# QFN-20_0_5mm.net
KiCad netlist of a schematic drawn in EAGLE
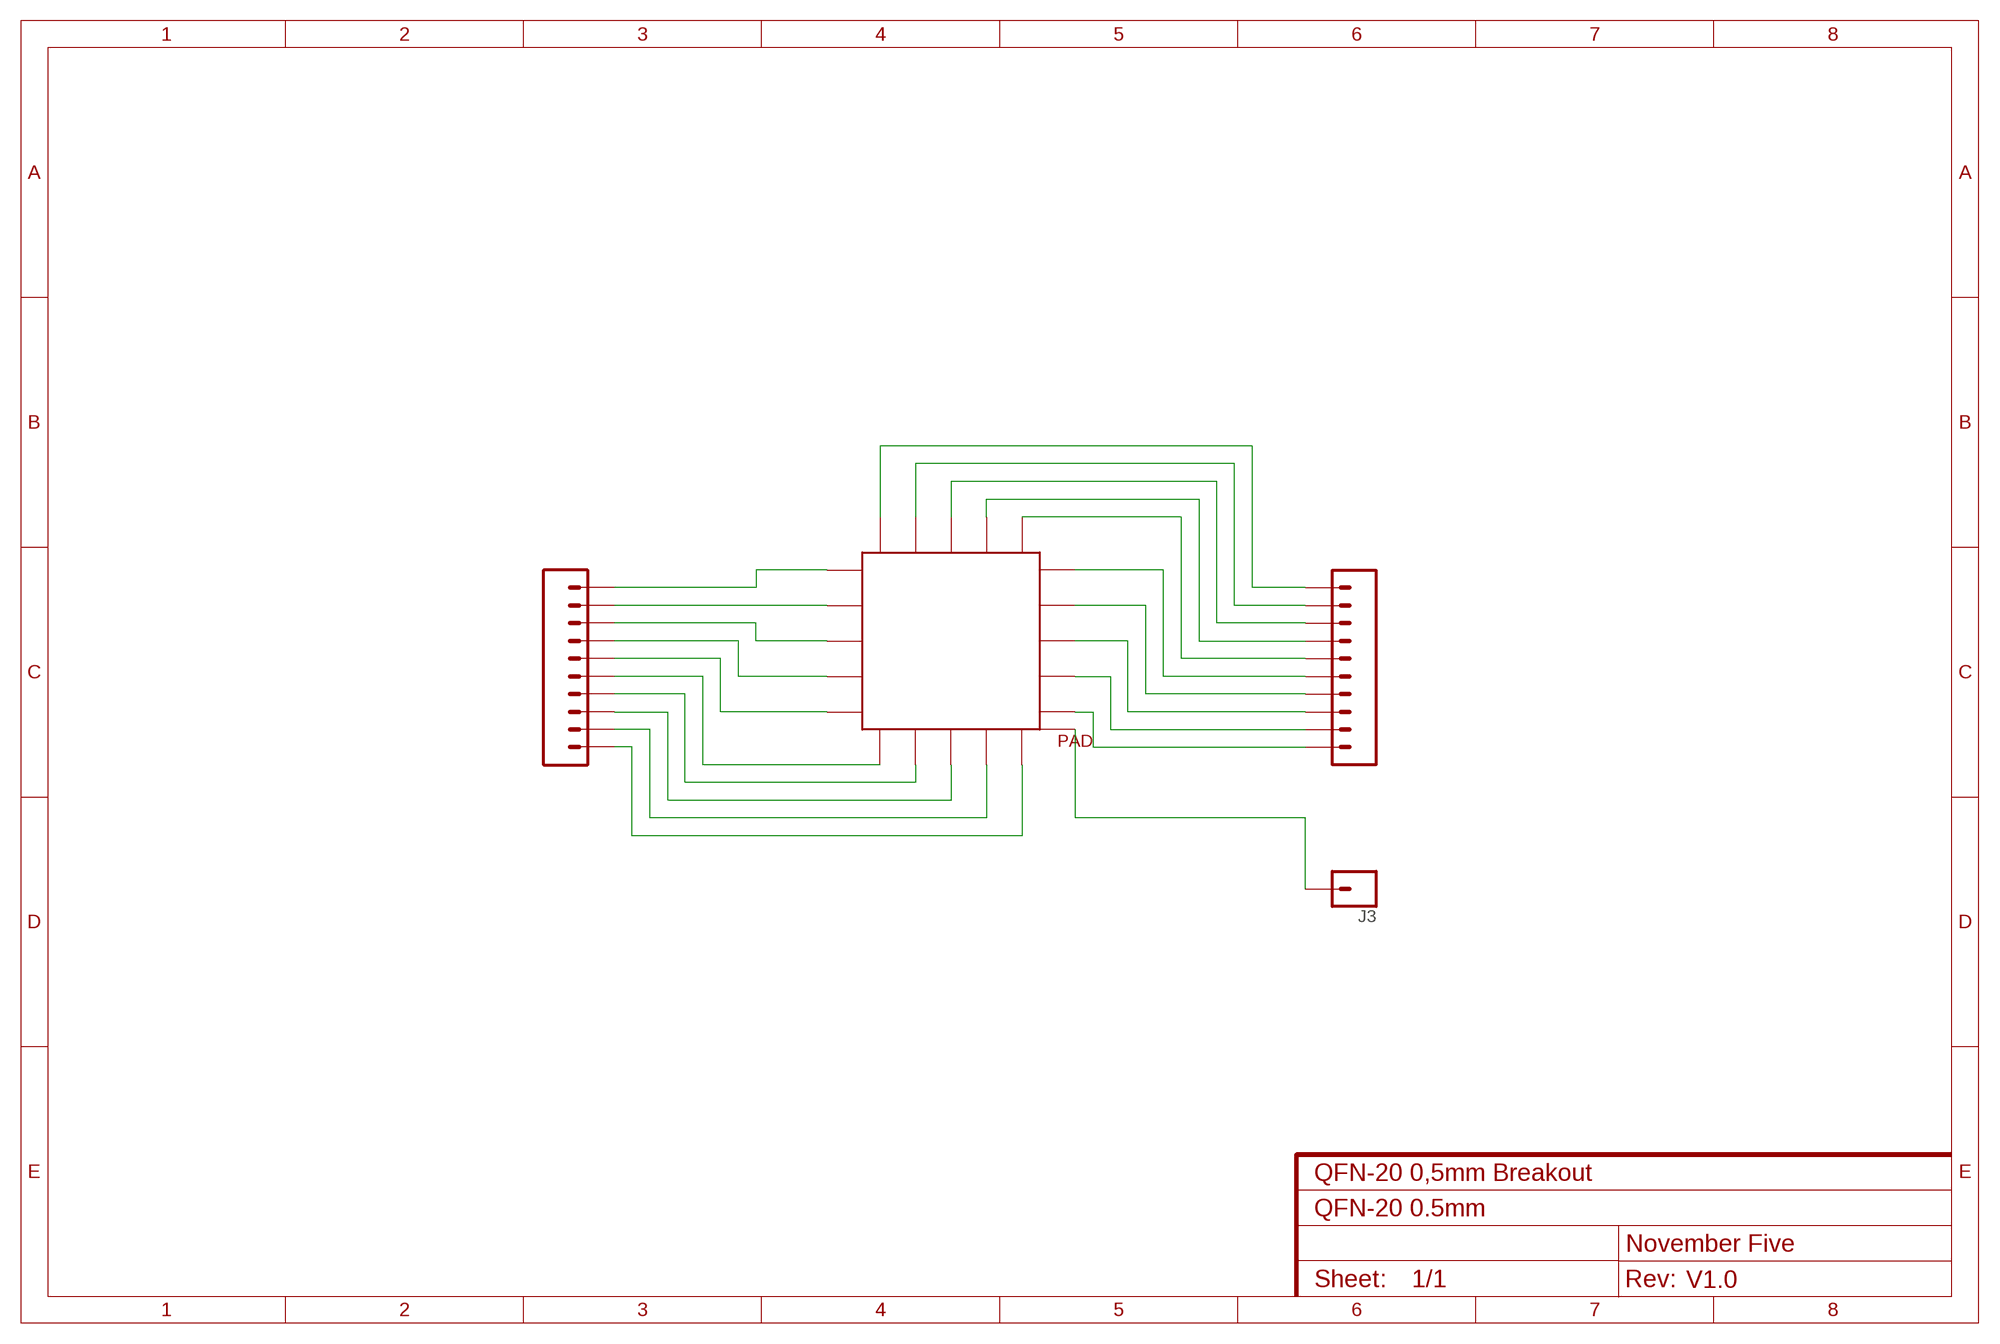
[diagram p0: schematic, sheet 1]

(export (version "E")
  (design (tool "Eeschema 10.0.6"))
  (components
    (comp (ref "J1")
      (value "CONN_10\"")
      (footprint "eagle-import:1X10")
      (libsource (lib "eagle-import") (part "CONN_10{dblquote}"))
    )
    (comp (ref "J2")
      (value "CONN_10\"")
      (footprint "eagle-import:1X10")
      (libsource (lib "eagle-import") (part "CONN_10{dblquote}"))
    )
    (comp (ref "J3")
      (value "CONN_01")
      (footprint "eagle-import:1X01")
      (libsource (lib "eagle-import") (part "CONN_01"))
    )
    (comp (ref "U$1")
      (value "QFN-20_0,5MM")
      (footprint "eagle-import:QFN20_0,5MM")
      (libsource (lib "eagle-import") (part "QFN-20_0,5MM"))
    )
  )
  (nets
    (net (code "1") (name "Net-(U$1-PAD)") (class "Default")
      (node (ref "J3") (pin "1") (pinfunction "1_1") (pintype "passive"))
      (node (ref "U$1") (pin "0") (pinfunction "PAD_0") (pintype "power_in"))
    )
    (net (code "2") (name "Net-(U$1-PIN1)") (class "Default")
      (node (ref "J1") (pin "1") (pinfunction "1_1") (pintype "passive"))
      (node (ref "U$1") (pin "1") (pinfunction "PIN1_1") (pintype "bidirectional"))
    )
    (net (code "3") (name "Net-(U$1-PIN2)") (class "Default")
      (node (ref "J1") (pin "2") (pinfunction "2_2") (pintype "passive"))
      (node (ref "U$1") (pin "2") (pinfunction "PIN2_2") (pintype "bidirectional"))
    )
    (net (code "4") (name "Net-(U$1-PIN3)") (class "Default")
      (node (ref "J1") (pin "3") (pinfunction "3_3") (pintype "passive"))
      (node (ref "U$1") (pin "3") (pinfunction "PIN3_3") (pintype "bidirectional"))
    )
    (net (code "5") (name "Net-(U$1-PIN4)") (class "Default")
      (node (ref "J1") (pin "4") (pinfunction "4_4") (pintype "passive"))
      (node (ref "U$1") (pin "4") (pinfunction "PIN4_4") (pintype "bidirectional"))
    )
    (net (code "6") (name "Net-(U$1-PIN5)") (class "Default")
      (node (ref "J1") (pin "5") (pinfunction "5_5") (pintype "passive"))
      (node (ref "U$1") (pin "5") (pinfunction "PIN5_5") (pintype "bidirectional"))
    )
    (net (code "7") (name "Net-(U$1-PIN6)") (class "Default")
      (node (ref "J1") (pin "6") (pinfunction "6_6") (pintype "passive"))
      (node (ref "U$1") (pin "6") (pinfunction "PIN6_6") (pintype "bidirectional"))
    )
    (net (code "8") (name "Net-(U$1-PIN7)") (class "Default")
      (node (ref "J1") (pin "7") (pinfunction "7_7") (pintype "passive"))
      (node (ref "U$1") (pin "7") (pinfunction "PIN7_7") (pintype "bidirectional"))
    )
    (net (code "9") (name "Net-(U$1-PIN8)") (class "Default")
      (node (ref "J1") (pin "8") (pinfunction "8_8") (pintype "passive"))
      (node (ref "U$1") (pin "8") (pinfunction "PIN8_8") (pintype "bidirectional"))
    )
    (net (code "10") (name "Net-(U$1-PIN9)") (class "Default")
      (node (ref "J1") (pin "9") (pinfunction "9_9") (pintype "passive"))
      (node (ref "U$1") (pin "9") (pinfunction "PIN9_9") (pintype "bidirectional"))
    )
    (net (code "11") (name "Net-(U$1-PIN10)") (class "Default")
      (node (ref "J1") (pin "10") (pinfunction "10_10") (pintype "passive"))
      (node (ref "U$1") (pin "10") (pinfunction "PIN10_10") (pintype "bidirectional"))
    )
    (net (code "12") (name "Net-(U$1-PIN11)") (class "Default")
      (node (ref "J2") (pin "10") (pinfunction "10_10") (pintype "passive"))
      (node (ref "U$1") (pin "11") (pinfunction "PIN11_11") (pintype "bidirectional"))
    )
    (net (code "13") (name "Net-(U$1-PIN12)") (class "Default")
      (node (ref "J2") (pin "9") (pinfunction "9_9") (pintype "passive"))
      (node (ref "U$1") (pin "12") (pinfunction "PIN12_12") (pintype "bidirectional"))
    )
    (net (code "14") (name "Net-(U$1-PIN13)") (class "Default")
      (node (ref "J2") (pin "8") (pinfunction "8_8") (pintype "passive"))
      (node (ref "U$1") (pin "13") (pinfunction "PIN13_13") (pintype "bidirectional"))
    )
    (net (code "15") (name "Net-(U$1-PIN14)") (class "Default")
      (node (ref "J2") (pin "7") (pinfunction "7_7") (pintype "passive"))
      (node (ref "U$1") (pin "14") (pinfunction "PIN14_14") (pintype "bidirectional"))
    )
    (net (code "16") (name "Net-(U$1-PIN15)") (class "Default")
      (node (ref "J2") (pin "6") (pinfunction "6_6") (pintype "passive"))
      (node (ref "U$1") (pin "15") (pinfunction "PIN15_15") (pintype "bidirectional"))
    )
    (net (code "17") (name "Net-(U$1-PIN16)") (class "Default")
      (node (ref "J2") (pin "5") (pinfunction "5_5") (pintype "passive"))
      (node (ref "U$1") (pin "16") (pinfunction "PIN16_16") (pintype "bidirectional"))
    )
    (net (code "18") (name "Net-(U$1-PIN17)") (class "Default")
      (node (ref "J2") (pin "4") (pinfunction "4_4") (pintype "passive"))
      (node (ref "U$1") (pin "17") (pinfunction "PIN17_17") (pintype "bidirectional"))
    )
    (net (code "19") (name "Net-(U$1-PIN18)") (class "Default")
      (node (ref "J2") (pin "3") (pinfunction "3_3") (pintype "passive"))
      (node (ref "U$1") (pin "18") (pinfunction "PIN18_18") (pintype "bidirectional"))
    )
    (net (code "20") (name "Net-(U$1-PIN19)") (class "Default")
      (node (ref "J2") (pin "2") (pinfunction "2_2") (pintype "passive"))
      (node (ref "U$1") (pin "19") (pinfunction "PIN19_19") (pintype "bidirectional"))
    )
    (net (code "21") (name "Net-(U$1-PIN20)") (class "Default")
      (node (ref "J2") (pin "1") (pinfunction "1_1") (pintype "passive"))
      (node (ref "U$1") (pin "20") (pinfunction "PIN20_20") (pintype "bidirectional"))
    )
  )
)
